# TCA_CLK_DIST.net
KiCad netlist of a schematic drawn in Altium Designer
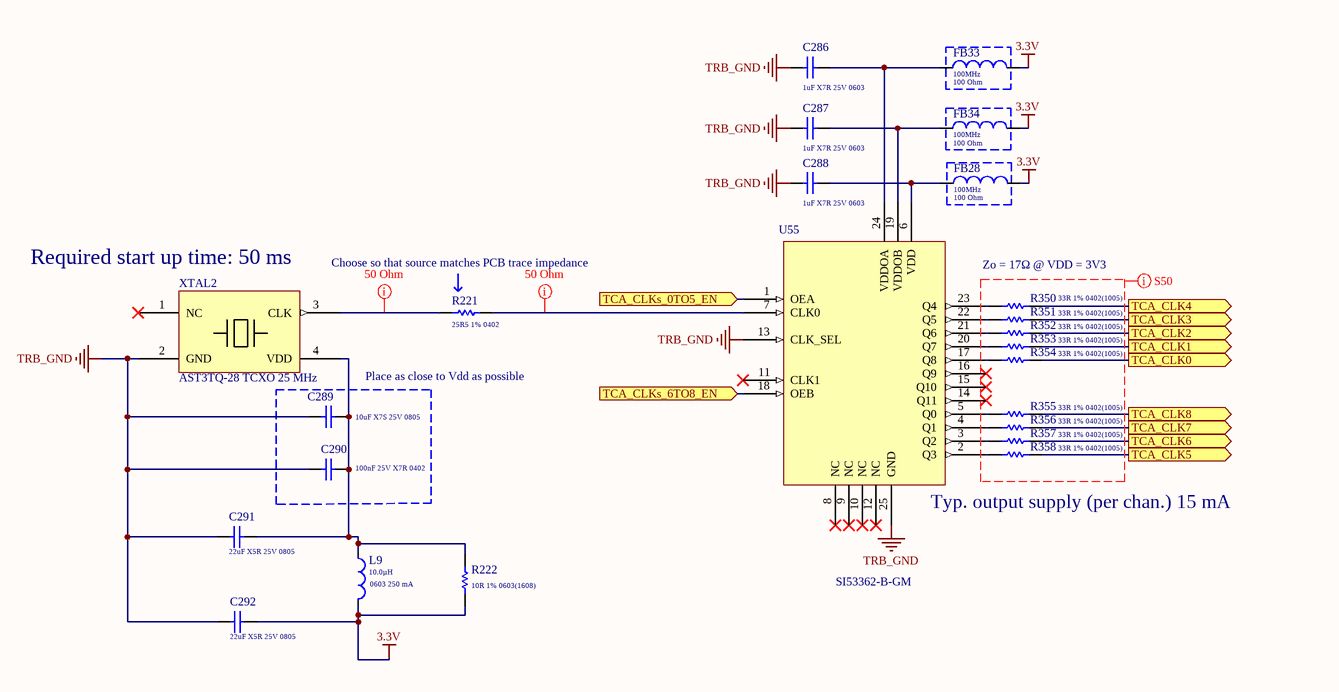
[diagram p0: TCA_CLK_DIST.SchDoc]

(export (version "E")
  (design (tool "Eeschema 10.0.6"))
  (components
    (comp (ref "C286")
      (value "Cap_Murata_GCJ188R71E105KA01J_1uF")
      (footprint "Cap_Murata_GCJ188R71E105KA01J_1uF")
      (description "CAP CER 1uF 25V X7R 0603")
      (fields (field (name "CAPACITANCE") "1uF X7R 25V 0603"))
      (libsource (lib "Cap_Murata_GCJ188R71E105KA01J_1uF") (part "Cap_Murata_GCJ188R71E105KA01J_1uF"))
    )
    (comp (ref "C287")
      (value "Cap_Murata_GCJ188R71E105KA01J_1uF")
      (footprint "Cap_Murata_GCJ188R71E105KA01J_1uF")
      (description "CAP CER 1uF 25V X7R 0603")
      (fields (field (name "CAPACITANCE") "1uF X7R 25V 0603"))
      (libsource (lib "Cap_Murata_GCJ188R71E105KA01J_1uF") (part "Cap_Murata_GCJ188R71E105KA01J_1uF"))
    )
    (comp (ref "C288")
      (value "Cap_Murata_GCJ188R71E105KA01J_1uF")
      (footprint "Cap_Murata_GCJ188R71E105KA01J_1uF")
      (description "CAP CER 1uF 25V X7R 0603")
      (fields (field (name "CAPACITANCE") "1uF X7R 25V 0603"))
      (libsource (lib "Cap_Murata_GCJ188R71E105KA01J_1uF") (part "Cap_Murata_GCJ188R71E105KA01J_1uF"))
    )
    (comp (ref "C289")
      (value "Cap_Murata_ GRM21BC71E106ME11L_10uF")
      (footprint "Cap_Murata_ GRM21BC71E106ME11L_10uF")
      (description "CAP CER 10uF 25V X7R 0805")
      (fields (field (name "CAPACITANCE") "10uF X7S 25V 0805"))
      (libsource (lib "Cap_Murata_ GRM21BC71E106ME11L_10uF") (part "Cap_Murata_ GRM21BC71E106ME11L_10uF"))
    )
    (comp (ref "C290")
      (value "Cap_Taiyo_Yuden_TMK105B7104KV-FR_100nF")
      (footprint "Cap_Taiyo_Yuden_TMK105B7104KV-FR_100nF")
      (description "CAP CER 100nF 25V X7R 0402")
      (fields (field (name "CAPACITANCE") "100nF 25V X7R 0402"))
      (libsource (lib "Cap_Taiyo_Yuden_TMK105B7104KV-FR_100nF") (part "Cap_Taiyo_Yuden_TMK105B7104KV-FR_100nF"))
    )
    (comp (ref "C291")
      (value "Cap_Murata_GRT21BR61E226ME13L_22uF")
      (footprint "Cap_Murata_GRT21BR61E226ME13L_22uF")
      (description "CAP CER 22uF 25V X5R 0805")
      (fields (field (name "CAPACITANCE") "22uF X5R 25V 0805"))
      (libsource (lib "Cap_Murata_GRT21BR61E226ME13L_22uF") (part "Cap_Murata_GRT21BR61E226ME13L_22uF"))
    )
    (comp (ref "C292")
      (value "Cap_Murata_GRT21BR61E226ME13L_22uF")
      (footprint "Cap_Murata_GRT21BR61E226ME13L_22uF")
      (description "CAP CER 22uF 25V X5R 0805")
      (fields (field (name "CAPACITANCE") "22uF X5R 25V 0805"))
      (libsource (lib "Cap_Murata_GRT21BR61E226ME13L_22uF") (part "Cap_Murata_GRT21BR61E226ME13L_22uF"))
    )
    (comp (ref "FB28")
      (value "742792731")
      (footprint "FB_Wurth_Electronics_742792731_100Ohms")
      (description "FB SMD 100 OHM 25% 1.2A 0402")
      (fields (field (name "MEASURING FREQUENCY") "100MHz") (field (name "IMPEDANCE") "100 Ohm"))
      (libsource (lib "FB_Wurth_Electronics_742792731_100Ohms") (part "FB_Wurth_Electronics_742792731_100Ohms"))
    )
    (comp (ref "FB33")
      (value "742792731")
      (footprint "FB_Wurth_Electronics_742792731_100Ohms")
      (description "FB SMD 100 OHM 25% 1.2A 0402")
      (fields (field (name "MEASURING FREQUENCY") "100MHz") (field (name "IMPEDANCE") "100 Ohm"))
      (libsource (lib "FB_Wurth_Electronics_742792731_100Ohms") (part "FB_Wurth_Electronics_742792731_100Ohms"))
    )
    (comp (ref "FB34")
      (value "742792731")
      (footprint "FB_Wurth_Electronics_742792731_100Ohms")
      (description "FB SMD 100 OHM 25% 1.2A 0402")
      (fields (field (name "MEASURING FREQUENCY") "100MHz") (field (name "IMPEDANCE") "100 Ohm"))
      (libsource (lib "FB_Wurth_Electronics_742792731_100Ohms") (part "FB_Wurth_Electronics_742792731_100Ohms"))
    )
    (comp (ref "L9")
      (value "0603 250 mA")
      (footprint "TDK_MLZ1608M100WT_0")
      (description "IND 10µH Shielded Multilayer Inductor 250mA 1.365 Ohm Max 0603 (1608 Metric)")
      (fields
        (field (name "PART NUMBER") "MLZ1608M100WT")
        (field (name "MANUFACTURER") "TDK")
        (field (name "INDUCTANCE") "10.0µH")
      )
      (libsource (lib "Ind_TDK_MLZ1608M100WT_10uH") (part "Ind_TDK_MLZ1608M100WT_eec"))
    )
    (comp (ref "R221")
      (value "25R5 1% 0402")
      (footprint "RESC0402(1005)_L")
      (description "25R5 0.063W 1% 0402 (1005 Metric)  SMD")
      (fields (field (name "TOLERANCE") "1 %") (field (name "POWER") "0.063 W"))
      (libsource (lib "Altium Content Vault") (part "RES"))
    )
    (comp (ref "R222")
      (value "10R 1% 0603(1608)")
      (footprint "RESC0603(1608)_L")
      (description "10R 0.1W 1% 0603 (1608 Metric)  SMD")
      (fields (field (name "TOLERANCE") "1 %") (field (name "POWER") "0.1 W"))
      (libsource (lib "Altium Content Vault") (part "RES"))
    )
    (comp (ref "R350")
      (value "33R 1% 0402(1005)")
      (footprint "RESC0402(1005)_L")
      (description "33R 0.063W 1% 0402 (1005 Metric)  SMD")
      (fields (field (name "TOLERANCE") "1 %") (field (name "POWER") "0.063 W"))
      (libsource (lib "Altium Content Vault") (part "RES"))
    )
    (comp (ref "R351")
      (value "33R 1% 0402(1005)")
      (footprint "RESC0402(1005)_L")
      (description "33R 0.063W 1% 0402 (1005 Metric)  SMD")
      (fields (field (name "TOLERANCE") "1 %") (field (name "POWER") "0.063 W"))
      (libsource (lib "Altium Content Vault") (part "RES"))
    )
    (comp (ref "R352")
      (value "33R 1% 0402(1005)")
      (footprint "RESC0402(1005)_L")
      (description "33R 0.063W 1% 0402 (1005 Metric)  SMD")
      (fields (field (name "TOLERANCE") "1 %") (field (name "POWER") "0.063 W"))
      (libsource (lib "Altium Content Vault") (part "RES"))
    )
    (comp (ref "R353")
      (value "33R 1% 0402(1005)")
      (footprint "RESC0402(1005)_L")
      (description "33R 0.063W 1% 0402 (1005 Metric)  SMD")
      (fields (field (name "TOLERANCE") "1 %") (field (name "POWER") "0.063 W"))
      (libsource (lib "Altium Content Vault") (part "RES"))
    )
    (comp (ref "R354")
      (value "33R 1% 0402(1005)")
      (footprint "RESC0402(1005)_L")
      (description "33R 0.063W 1% 0402 (1005 Metric)  SMD")
      (fields (field (name "TOLERANCE") "1 %") (field (name "POWER") "0.063 W"))
      (libsource (lib "Altium Content Vault") (part "RES"))
    )
    (comp (ref "R355")
      (value "33R 1% 0402(1005)")
      (footprint "RESC0402(1005)_L")
      (description "33R 0.063W 1% 0402 (1005 Metric)  SMD")
      (fields (field (name "TOLERANCE") "1 %") (field (name "POWER") "0.063 W"))
      (libsource (lib "Altium Content Vault") (part "RES"))
    )
    (comp (ref "R356")
      (value "33R 1% 0402(1005)")
      (footprint "RESC0402(1005)_L")
      (description "33R 0.063W 1% 0402 (1005 Metric)  SMD")
      (fields (field (name "TOLERANCE") "1 %") (field (name "POWER") "0.063 W"))
      (libsource (lib "Altium Content Vault") (part "RES"))
    )
    (comp (ref "R357")
      (value "33R 1% 0402(1005)")
      (footprint "RESC0402(1005)_L")
      (description "33R 0.063W 1% 0402 (1005 Metric)  SMD")
      (fields (field (name "TOLERANCE") "1 %") (field (name "POWER") "0.063 W"))
      (libsource (lib "Altium Content Vault") (part "RES"))
    )
    (comp (ref "R358")
      (value "33R 1% 0402(1005)")
      (footprint "RESC0402(1005)_L")
      (description "33R 0.063W 1% 0402 (1005 Metric)  SMD")
      (fields (field (name "TOLERANCE") "1 %") (field (name "POWER") "0.063 W"))
      (libsource (lib "Altium Content Vault") (part "RES"))
    )
    (comp (ref "U55")
      (value "SI53362-B-GM")
      (footprint "Si53362")
      (description "Clock Buffer LVCMOS 2:12 buffer (200MHz), 2:1 LVCMOS input max, output enable (QFN24)")
      (libsource (lib "SI53362") (part "SI53362-B-GM"))
    )
    (comp (ref "XTAL2")
      (value "AST3TQ-28 TCXO 25 MHz")
      (footprint "XTAL_ASDM1-25.000MHZ-LC-T")
      (description "TCXO Oscillators 25MHz 3.3Volt LVCMOS 0.280 ppm -40C 85C")
      (libsource (lib "XTAL_Abracaon_AST3TQ-T-25.000MHz-28") (part "AST3TQ-28"))
    )
  )
  (nets
    (net (code "1") (name "/TCA_CLK0") (class "Default")
      (node (ref "R354") (pin "2") (pinfunction "2_2") (pintype "passive"))
    )
    (net (code "2") (name "/TCA_CLK1") (class "Default")
      (node (ref "R353") (pin "2") (pinfunction "2_2") (pintype "passive"))
    )
    (net (code "3") (name "/TCA_CLK2") (class "Default")
      (node (ref "R352") (pin "2") (pinfunction "2_2") (pintype "passive"))
    )
    (net (code "4") (name "/TCA_CLK3") (class "Default")
      (node (ref "R351") (pin "2") (pinfunction "2_2") (pintype "passive"))
    )
    (net (code "5") (name "/TCA_CLK4") (class "Default")
      (node (ref "R350") (pin "2") (pinfunction "2_2") (pintype "passive"))
    )
    (net (code "6") (name "/TCA_CLK5") (class "Default")
      (node (ref "R358") (pin "2") (pinfunction "2_2") (pintype "passive"))
    )
    (net (code "7") (name "/TCA_CLK6") (class "Default")
      (node (ref "R357") (pin "2") (pinfunction "2_2") (pintype "passive"))
    )
    (net (code "8") (name "/TCA_CLK7") (class "Default")
      (node (ref "R356") (pin "2") (pinfunction "2_2") (pintype "passive"))
    )
    (net (code "9") (name "/TCA_CLK8") (class "Default")
      (node (ref "R355") (pin "2") (pinfunction "2_2") (pintype "passive"))
    )
    (net (code "10") (name "/TCA_CLKs_0TO5_EN") (class "Default")
      (node (ref "U55") (pin "1") (pinfunction "OEA_1") (pintype "input"))
    )
    (net (code "11") (name "/TCA_CLKs_6TO8_EN") (class "Default")
      (node (ref "U55") (pin "18") (pinfunction "OEB_18") (pintype "input"))
    )
    (net (code "12") (name "3.3V") (class "Default")
      (node (ref "C292") (pin "2") (pinfunction "2_2") (pintype "passive"))
      (node (ref "FB28") (pin "2") (pinfunction "2_2") (pintype "passive"))
      (node (ref "FB33") (pin "2") (pinfunction "2_2") (pintype "passive"))
      (node (ref "FB34") (pin "2") (pinfunction "2_2") (pintype "passive"))
      (node (ref "L9") (pin "2") (pinfunction "2_2") (pintype "passive"))
      (node (ref "R222") (pin "1") (pinfunction "1_1") (pintype "passive"))
    )
    (net (code "13") (name "Net-(U55-CLK0)") (class "Default")
      (node (ref "R221") (pin "2") (pinfunction "2_2") (pintype "passive"))
      (node (ref "U55") (pin "7") (pinfunction "CLK0_7") (pintype "input"))
    )
    (net (code "14") (name "Net-(U55-Q0)") (class "Default")
      (node (ref "R355") (pin "1") (pinfunction "1_1") (pintype "passive"))
      (node (ref "U55") (pin "5") (pinfunction "Q0_5") (pintype "output"))
    )
    (net (code "15") (name "Net-(U55-Q1)") (class "Default")
      (node (ref "R356") (pin "1") (pinfunction "1_1") (pintype "passive"))
      (node (ref "U55") (pin "4") (pinfunction "Q1_4") (pintype "output"))
    )
    (net (code "16") (name "Net-(U55-Q2)") (class "Default")
      (node (ref "R357") (pin "1") (pinfunction "1_1") (pintype "passive"))
      (node (ref "U55") (pin "3") (pinfunction "Q2_3") (pintype "output"))
    )
    (net (code "17") (name "Net-(U55-Q3)") (class "Default")
      (node (ref "R358") (pin "1") (pinfunction "1_1") (pintype "passive"))
      (node (ref "U55") (pin "2") (pinfunction "Q3_2") (pintype "output"))
    )
    (net (code "18") (name "Net-(U55-Q4)") (class "Default")
      (node (ref "R350") (pin "1") (pinfunction "1_1") (pintype "passive"))
      (node (ref "U55") (pin "23") (pinfunction "Q4_23") (pintype "output"))
    )
    (net (code "19") (name "Net-(U55-Q5)") (class "Default")
      (node (ref "R351") (pin "1") (pinfunction "1_1") (pintype "passive"))
      (node (ref "U55") (pin "22") (pinfunction "Q5_22") (pintype "output"))
    )
    (net (code "20") (name "Net-(U55-Q6)") (class "Default")
      (node (ref "R352") (pin "1") (pinfunction "1_1") (pintype "passive"))
      (node (ref "U55") (pin "21") (pinfunction "Q6_21") (pintype "output"))
    )
    (net (code "21") (name "Net-(U55-Q7)") (class "Default")
      (node (ref "R353") (pin "1") (pinfunction "1_1") (pintype "passive"))
      (node (ref "U55") (pin "20") (pinfunction "Q7_20") (pintype "output"))
    )
    (net (code "22") (name "Net-(U55-Q8)") (class "Default")
      (node (ref "R354") (pin "1") (pinfunction "1_1") (pintype "passive"))
      (node (ref "U55") (pin "17") (pinfunction "Q8_17") (pintype "output"))
    )
    (net (code "23") (name "Net-(U55-VDD)") (class "Default")
      (node (ref "C288") (pin "1") (pinfunction "1_1") (pintype "passive"))
      (node (ref "FB28") (pin "1") (pinfunction "1_1") (pintype "passive"))
      (node (ref "U55") (pin "6") (pinfunction "VDD_6") (pintype "power_in"))
    )
    (net (code "24") (name "Net-(U55-VDDOA)") (class "Default")
      (node (ref "C286") (pin "1") (pinfunction "1_1") (pintype "passive"))
      (node (ref "FB33") (pin "1") (pinfunction "1_1") (pintype "passive"))
      (node (ref "U55") (pin "24") (pinfunction "VDDOA_24") (pintype "power_in"))
    )
    (net (code "25") (name "Net-(U55-VDDOB)") (class "Default")
      (node (ref "C287") (pin "1") (pinfunction "1_1") (pintype "passive"))
      (node (ref "FB34") (pin "1") (pinfunction "1_1") (pintype "passive"))
      (node (ref "U55") (pin "19") (pinfunction "VDDOB_19") (pintype "power_in"))
    )
    (net (code "26") (name "Net-(XTAL2-CLK)") (class "Default")
      (node (ref "R221") (pin "1") (pinfunction "1_1") (pintype "passive"))
      (node (ref "XTAL2") (pin "3") (pinfunction "CLK_3") (pintype "output"))
    )
    (net (code "27") (name "Net-(XTAL2-VDD)") (class "Default")
      (node (ref "C289") (pin "2") (pinfunction "2_2") (pintype "passive"))
      (node (ref "C290") (pin "1") (pinfunction "1_1") (pintype "passive"))
      (node (ref "C291") (pin "2") (pinfunction "2_2") (pintype "passive"))
      (node (ref "L9") (pin "1") (pinfunction "1_1") (pintype "passive"))
      (node (ref "R222") (pin "2") (pinfunction "2_2") (pintype "passive"))
      (node (ref "XTAL2") (pin "4") (pinfunction "VDD_4") (pintype "power_in"))
    )
    (net (code "28") (name "TRB_GND") (class "Default")
      (node (ref "C286") (pin "2") (pinfunction "2_2") (pintype "passive"))
      (node (ref "C287") (pin "2") (pinfunction "2_2") (pintype "passive"))
      (node (ref "C288") (pin "2") (pinfunction "2_2") (pintype "passive"))
      (node (ref "C289") (pin "1") (pinfunction "1_1") (pintype "passive"))
      (node (ref "C290") (pin "2") (pinfunction "2_2") (pintype "passive"))
      (node (ref "C291") (pin "1") (pinfunction "1_1") (pintype "passive"))
      (node (ref "C292") (pin "1") (pinfunction "1_1") (pintype "passive"))
      (node (ref "U55") (pin "13") (pinfunction "CLK_SEL_13") (pintype "input"))
      (node (ref "U55") (pin "25") (pinfunction "GND_25") (pintype "passive"))
      (node (ref "XTAL2") (pin "2") (pinfunction "GND_2") (pintype "passive"))
    )
    (net (code "29") (name "unconnected-(U55-CLK1-Pad11)") (class "Default")
      (node (ref "U55") (pin "11") (pinfunction "CLK1_11") (pintype "input+no_connect"))
    )
    (net (code "30") (name "unconnected-(U55-NC-Pad8)") (class "Default")
      (node (ref "U55") (pin "8") (pinfunction "NC_8") (pintype "passive+no_connect"))
    )
    (net (code "31") (name "unconnected-(U55-NC-Pad9)") (class "Default")
      (node (ref "U55") (pin "9") (pinfunction "NC_9") (pintype "passive+no_connect"))
    )
    (net (code "32") (name "unconnected-(U55-NC-Pad10)") (class "Default")
      (node (ref "U55") (pin "10") (pinfunction "NC_10") (pintype "passive+no_connect"))
    )
    (net (code "33") (name "unconnected-(U55-NC-Pad12)") (class "Default")
      (node (ref "U55") (pin "12") (pinfunction "NC_12") (pintype "passive+no_connect"))
    )
    (net (code "34") (name "unconnected-(U55-Q9-Pad16)") (class "Default")
      (node (ref "U55") (pin "16") (pinfunction "Q9_16") (pintype "output+no_connect"))
    )
    (net (code "35") (name "unconnected-(U55-Q10-Pad15)") (class "Default")
      (node (ref "U55") (pin "15") (pinfunction "Q10_15") (pintype "output+no_connect"))
    )
    (net (code "36") (name "unconnected-(U55-Q11-Pad14)") (class "Default")
      (node (ref "U55") (pin "14") (pinfunction "Q11_14") (pintype "output+no_connect"))
    )
    (net (code "37") (name "unconnected-(XTAL2-NC-Pad1)") (class "Default")
      (node (ref "XTAL2") (pin "1") (pinfunction "NC_1") (pintype "passive+no_connect"))
    )
  )
)
